# ProPrj_2026_05_12_drone_2026-05-23.net
KiCad netlist of a schematic drawn in EasyEDA Pro
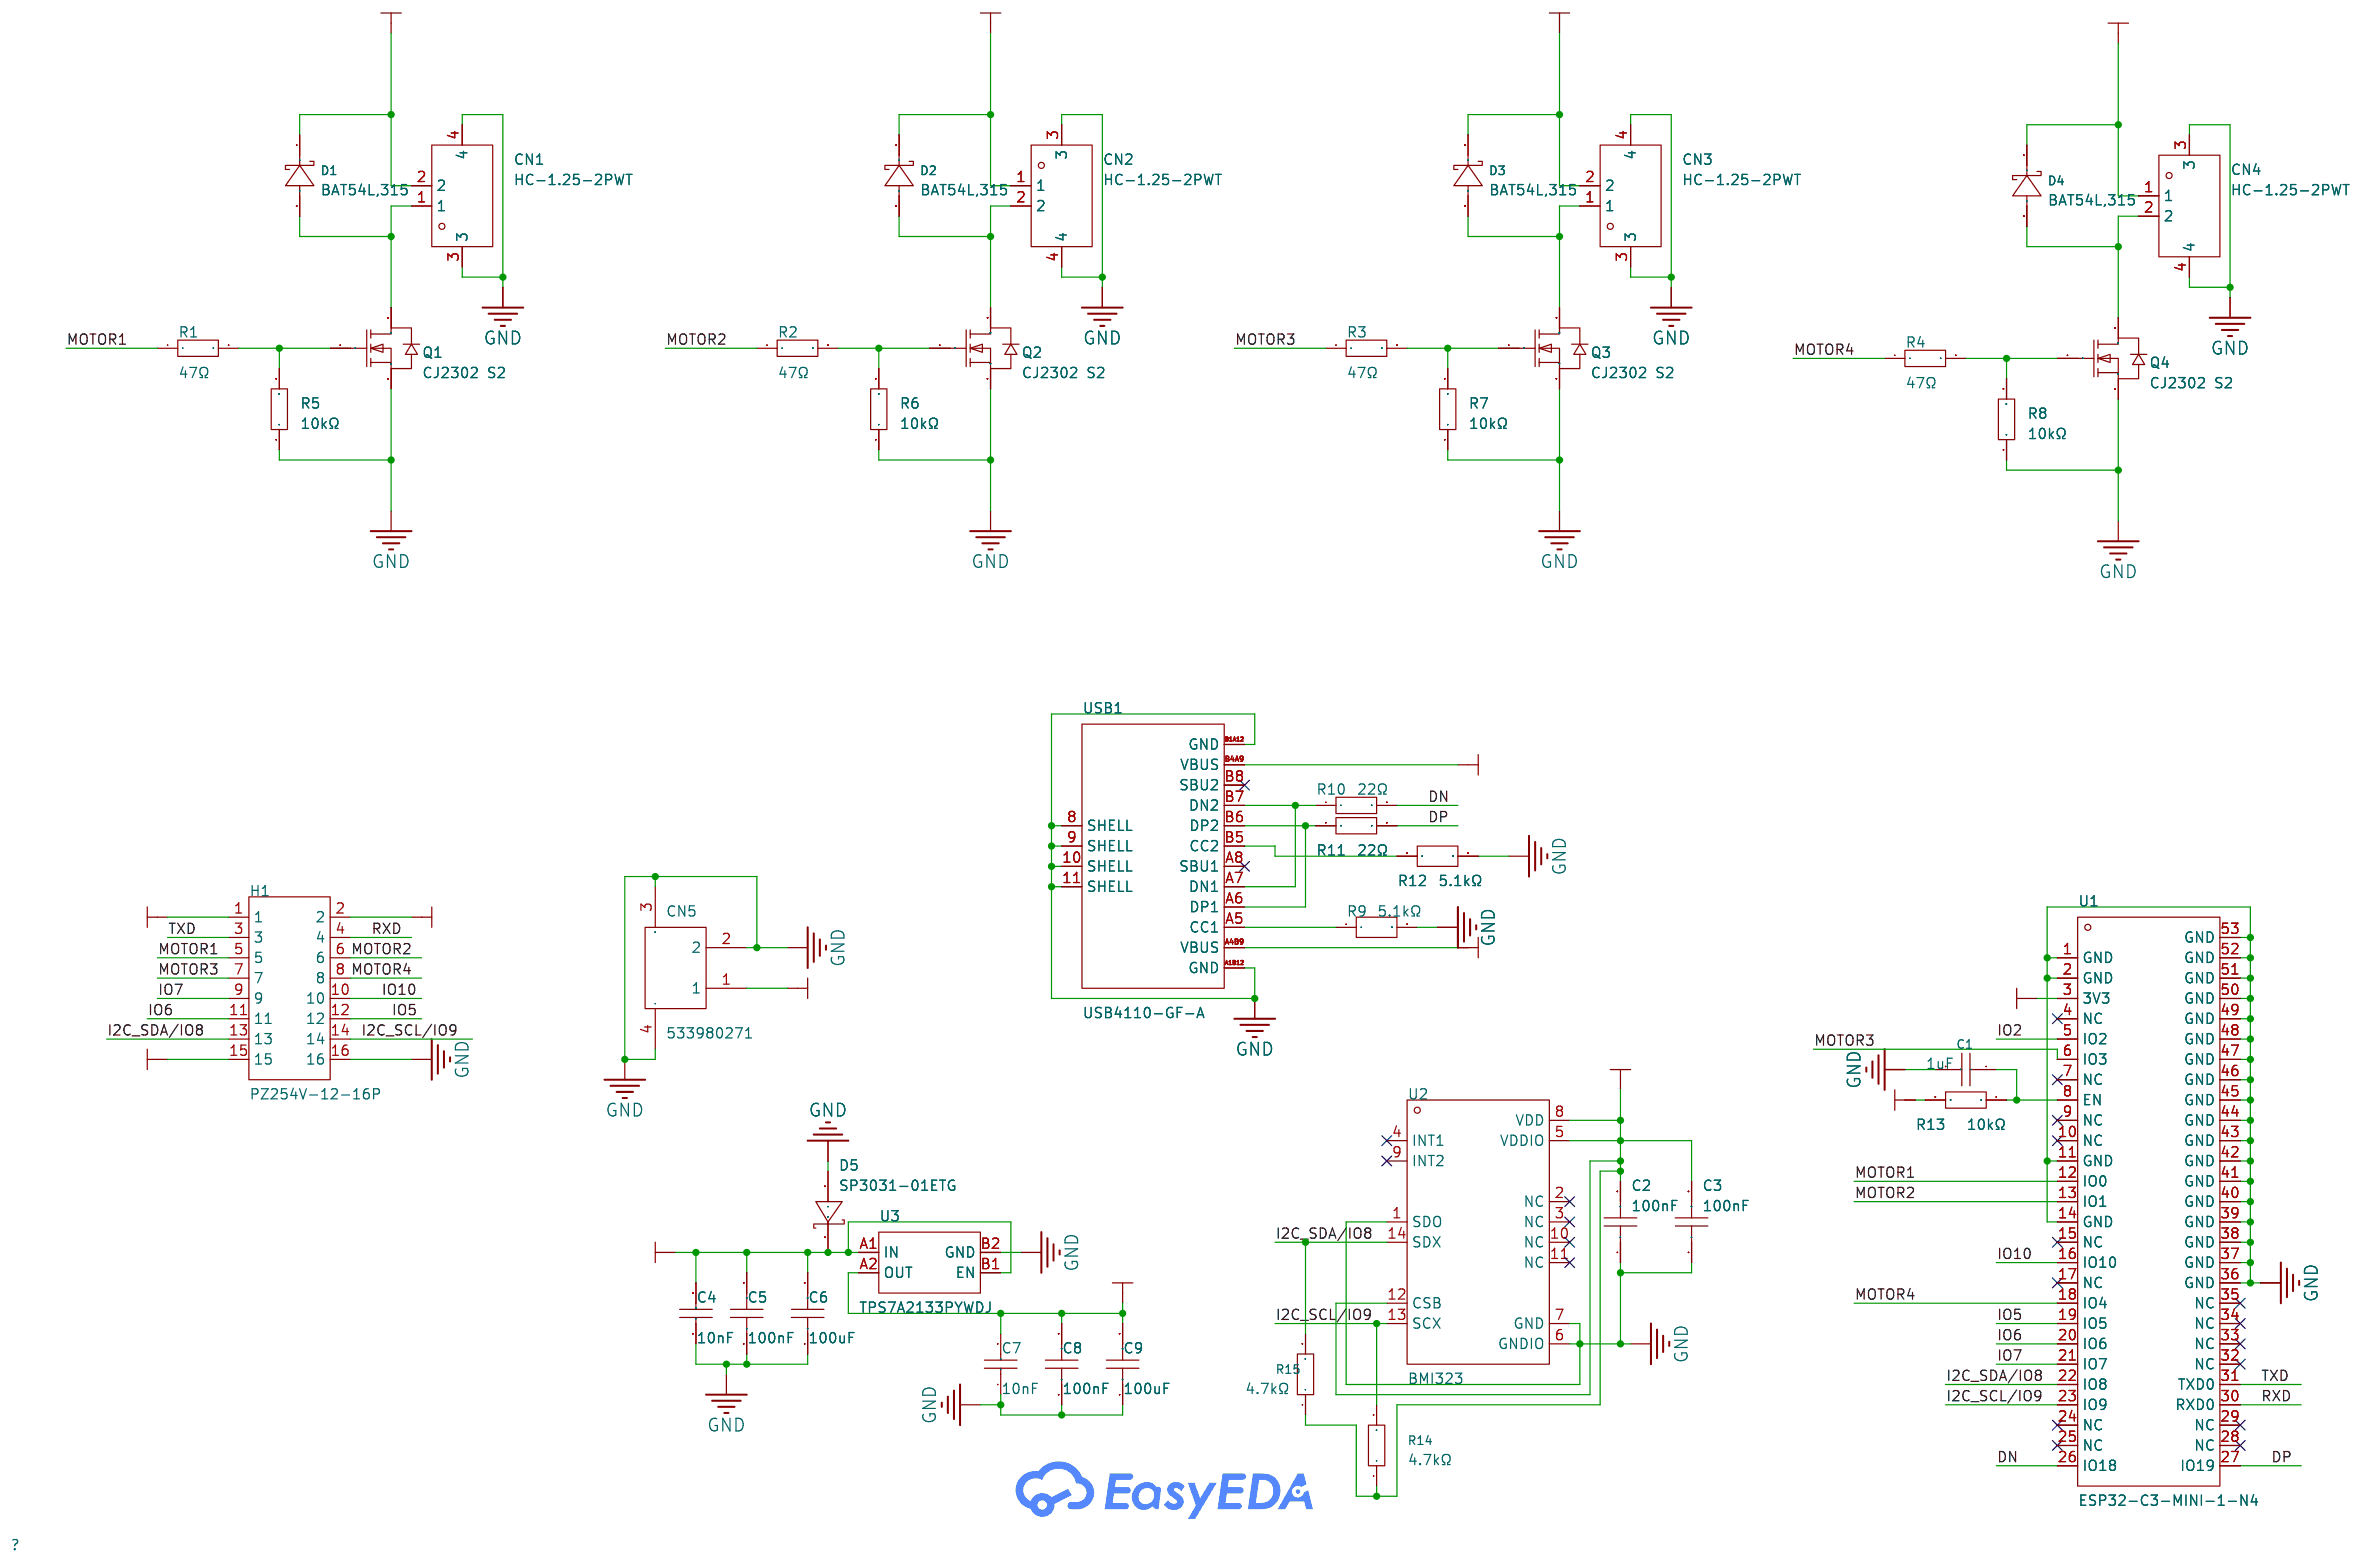
[diagram p0: schematic sheet]

(export (version "E")
  (design (tool "Eeschema 10.0.6"))
  (components
    (comp (ref "C1")
      (value "1uF")
      (footprint "easyedapro:C0402")
      (description "Capacitance:1uF Tolerance:±10% Tolerance:±10% Voltage Rating:16V Temperature Coefficient:X5R")
      (fields
        (field (name "Manufacturer Part") "CL05A105KO5NNNC")
        (field (name "Manufacturer") "SAMSUNG(三星)")
      )
      (libsource (lib "easyedapro") (part "CL05A105KO5NNNC"))
    )
    (comp (ref "C2")
      (value "100nF")
      (footprint "easyedapro:C0402")
      (fields
        (field (name "Manufacturer Part") "CL05B104KO5NNNC")
        (field (name "Manufacturer") "SAMSUNG(三星)")
      )
      (libsource (lib "easyedapro") (part "CL05B104KO5NNNC"))
    )
    (comp (ref "C3")
      (value "100nF")
      (footprint "easyedapro:C0402")
      (fields
        (field (name "Manufacturer Part") "CL05B104KO5NNNC")
        (field (name "Manufacturer") "SAMSUNG(三星)")
      )
      (libsource (lib "easyedapro") (part "CL05B104KO5NNNC"))
    )
    (comp (ref "C4")
      (value "10nF")
      (footprint "easyedapro:C0402")
      (description "Capacitance:10nF Tolerance:±10% Tolerance:±10% Voltage Rating:50V Temperature Coefficient:X7R")
      (fields
        (field (name "Manufacturer Part") "CL05B103KB5NNNC")
        (field (name "Manufacturer") "SAMSUNG(三星)")
      )
      (libsource (lib "easyedapro") (part "CL05B103KB5NNNC"))
    )
    (comp (ref "C5")
      (value "100nF")
      (footprint "easyedapro:C0603")
      (description "Capacitance:100nF Tolerance:±10% Tolerance:±10% Voltage Rating:50V Temperature Coefficient:X7R")
      (fields
        (field (name "Manufacturer Part") "CC0603KRX7R9BB104")
        (field (name "Manufacturer") "YAGEO(国巨)")
      )
      (libsource (lib "easyedapro") (part "CC0603KRX7R9BB104"))
    )
    (comp (ref "C6")
      (value "100uF")
      (footprint "easyedapro:C1206")
      (description "Capacitance:100uF Tolerance:±20% Tolerance:±20% Voltage Rating:10V Temperature Coefficient:X5R")
      (fields
        (field (name "Manufacturer Part") "HGC1206R5107M100NSPJ")
        (field (name "Manufacturer") "Chinocera(华瓷)")
      )
      (libsource (lib "easyedapro") (part "HGC1206R5107M100NSPJ"))
    )
    (comp (ref "C7")
      (value "10nF")
      (footprint "easyedapro:C0402")
      (description "Capacitance:10nF Tolerance:±10% Tolerance:±10% Voltage Rating:50V Temperature Coefficient:X7R")
      (fields
        (field (name "Manufacturer Part") "CL05B103KB5NNNC")
        (field (name "Manufacturer") "SAMSUNG(三星)")
      )
      (libsource (lib "easyedapro") (part "CL05B103KB5NNNC"))
    )
    (comp (ref "C8")
      (value "100nF")
      (footprint "easyedapro:C0603")
      (description "Capacitance:100nF Tolerance:±10% Tolerance:±10% Voltage Rating:50V Temperature Coefficient:X7R")
      (fields
        (field (name "Manufacturer Part") "CC0603KRX7R9BB104")
        (field (name "Manufacturer") "YAGEO(国巨)")
      )
      (libsource (lib "easyedapro") (part "CC0603KRX7R9BB104"))
    )
    (comp (ref "C9")
      (value "100uF")
      (footprint "easyedapro:C1206")
      (description "Capacitance:100uF Tolerance:±20% Tolerance:±20% Voltage Rating:10V Temperature Coefficient:X5R")
      (fields
        (field (name "Manufacturer Part") "HGC1206R5107M100NSPJ")
        (field (name "Manufacturer") "Chinocera(华瓷)")
      )
      (libsource (lib "easyedapro") (part "HGC1206R5107M100NSPJ"))
    )
    (comp (ref "CN1")
      (value "HC-1.25-2PWT")
      (footprint "easyedapro:CONN-SMD_2P-P1.25-HC-1.25-2PWT")
      (fields (field (name "Manufacturer") "HCTL(华灿天禄)"))
      (libsource (lib "easyedapro") (part "HC-1.25-2PWT"))
    )
    (comp (ref "CN2")
      (value "HC-1.25-2PWT")
      (footprint "easyedapro:CONN-SMD_2P-P1.25-HC-1.25-2PWT")
      (fields (field (name "Manufacturer") "HCTL(华灿天禄)"))
      (libsource (lib "easyedapro") (part "HC-1.25-2PWT"))
    )
    (comp (ref "CN3")
      (value "HC-1.25-2PWT")
      (footprint "easyedapro:CONN-SMD_2P-P1.25-HC-1.25-2PWT")
      (fields (field (name "Manufacturer") "HCTL(华灿天禄)"))
      (libsource (lib "easyedapro") (part "HC-1.25-2PWT"))
    )
    (comp (ref "CN4")
      (value "HC-1.25-2PWT")
      (footprint "easyedapro:CONN-SMD_2P-P1.25-HC-1.25-2PWT")
      (fields (field (name "Manufacturer") "HCTL(华灿天禄)"))
      (libsource (lib "easyedapro") (part "HC-1.25-2PWT"))
    )
    (comp (ref "CN5")
      (value "533980271")
      (footprint "easyedapro:CONN-SMD_2P-P1.25_053398-0X71")
      (fields (field (name "Manufacturer") "MOLEX"))
      (libsource (lib "easyedapro") (part "0533980271"))
    )
    (comp (ref "D1")
      (value "BAT54L,315")
      (footprint "easyedapro:DFN1006-2L-RD")
      (fields (field (name "Manufacturer") "Nexperia(安世)"))
      (libsource (lib "easyedapro") (part "BAT54L,315"))
    )
    (comp (ref "D2")
      (value "BAT54L,315")
      (footprint "easyedapro:DFN1006-2L-RD")
      (fields (field (name "Manufacturer") "Nexperia(安世)"))
      (libsource (lib "easyedapro") (part "BAT54L,315"))
    )
    (comp (ref "D3")
      (value "BAT54L,315")
      (footprint "easyedapro:DFN1006-2L-RD")
      (fields (field (name "Manufacturer") "Nexperia(安世)"))
      (libsource (lib "easyedapro") (part "BAT54L,315"))
    )
    (comp (ref "D4")
      (value "BAT54L,315")
      (footprint "easyedapro:DFN1006-2L-RD")
      (fields (field (name "Manufacturer") "Nexperia(安世)"))
      (libsource (lib "easyedapro") (part "BAT54L,315"))
    )
    (comp (ref "D5")
      (value "SP3031-01ETG")
      (footprint "easyedapro:SOD-882_L1.0-W0.6-RD")
      (fields (field (name "Manufacturer") "Littelfuse(美国力特)"))
      (libsource (lib "easyedapro") (part "SP3031-01ETG"))
    )
    (comp (ref "H1")
      (value "PZ254V-12-16P")
      (footprint "easyedapro:HDR-TH_16P-P2.54-V-M-R2-C8-S2.54")
      (fields (field (name "Manufacturer") "XFCN(兴飞)"))
      (libsource (lib "easyedapro") (part "PZ254V-12-16P"))
    )
    (comp (ref "Q1")
      (value "CJ2302 S2")
      (footprint "easyedapro:SOT-23-3_L3.0-W1.7-P0.95-LS2.9-BR")
      (fields (field (name "Manufacturer") "CJ(江苏长电/长晶)"))
      (libsource (lib "easyedapro") (part "CJ2302 S2"))
    )
    (comp (ref "Q2")
      (value "CJ2302 S2")
      (footprint "easyedapro:SOT-23-3_L3.0-W1.7-P0.95-LS2.9-BR")
      (fields (field (name "Manufacturer") "CJ(江苏长电/长晶)"))
      (libsource (lib "easyedapro") (part "CJ2302 S2"))
    )
    (comp (ref "Q3")
      (value "CJ2302 S2")
      (footprint "easyedapro:SOT-23-3_L3.0-W1.7-P0.95-LS2.9-BR")
      (fields (field (name "Manufacturer") "CJ(江苏长电/长晶)"))
      (libsource (lib "easyedapro") (part "CJ2302 S2"))
    )
    (comp (ref "Q4")
      (value "CJ2302 S2")
      (footprint "easyedapro:SOT-23-3_L3.0-W1.7-P0.95-LS2.9-BR")
      (fields (field (name "Manufacturer") "CJ(江苏长电/长晶)"))
      (libsource (lib "easyedapro") (part "CJ2302 S2"))
    )
    (comp (ref "R1")
      (value "47Ω")
      (footprint "easyedapro:R0402")
      (fields (field (name "Manufacturer Part") "RC0402FR-0747RL") (field (name "Manufacturer") "YAGEO(国巨)"))
      (libsource (lib "easyedapro") (part "RC0402FR-0747RL"))
    )
    (comp (ref "R2")
      (value "47Ω")
      (footprint "easyedapro:R0402")
      (fields (field (name "Manufacturer Part") "RC0402FR-0747RL") (field (name "Manufacturer") "YAGEO(国巨)"))
      (libsource (lib "easyedapro") (part "RC0402FR-0747RL"))
    )
    (comp (ref "R3")
      (value "47Ω")
      (footprint "easyedapro:R0402")
      (fields (field (name "Manufacturer Part") "RC0402FR-0747RL") (field (name "Manufacturer") "YAGEO(国巨)"))
      (libsource (lib "easyedapro") (part "RC0402FR-0747RL"))
    )
    (comp (ref "R4")
      (value "47Ω")
      (footprint "easyedapro:R0402")
      (fields (field (name "Manufacturer Part") "RC0402FR-0747RL") (field (name "Manufacturer") "YAGEO(国巨)"))
      (libsource (lib "easyedapro") (part "RC0402FR-0747RL"))
    )
    (comp (ref "R5")
      (value "10kΩ")
      (footprint "easyedapro:R0402")
      (fields (field (name "Manufacturer Part") "RC0402FR-0710KL") (field (name "Manufacturer") "YAGEO(国巨)"))
      (libsource (lib "easyedapro") (part "RC0402FR-0710KL"))
    )
    (comp (ref "R6")
      (value "10kΩ")
      (footprint "easyedapro:R0402")
      (fields (field (name "Manufacturer Part") "RC0402FR-0710KL") (field (name "Manufacturer") "YAGEO(国巨)"))
      (libsource (lib "easyedapro") (part "RC0402FR-0710KL"))
    )
    (comp (ref "R7")
      (value "10kΩ")
      (footprint "easyedapro:R0402")
      (fields (field (name "Manufacturer Part") "RC0402FR-0710KL") (field (name "Manufacturer") "YAGEO(国巨)"))
      (libsource (lib "easyedapro") (part "RC0402FR-0710KL"))
    )
    (comp (ref "R8")
      (value "10kΩ")
      (footprint "easyedapro:R0402")
      (fields (field (name "Manufacturer Part") "RC0402FR-0710KL") (field (name "Manufacturer") "YAGEO(国巨)"))
      (libsource (lib "easyedapro") (part "RC0402FR-0710KL"))
    )
    (comp (ref "R9")
      (value "5.1kΩ")
      (footprint "easyedapro:R0603")
      (fields (field (name "Manufacturer Part") "FRC0603F5101TS") (field (name "Manufacturer") "FOJAN(富捷)"))
      (libsource (lib "easyedapro") (part "FRC0603F5101TS"))
    )
    (comp (ref "R10")
      (value "22Ω")
      (footprint "easyedapro:R0603")
      (fields
        (field (name "Manufacturer Part") "0603WAF220JT5E")
        (field (name "Manufacturer") "UNI-ROYAL(厚声)")
      )
      (libsource (lib "easyedapro") (part "0603WAF220JT5E"))
    )
    (comp (ref "R11")
      (value "22Ω")
      (footprint "easyedapro:R0603")
      (fields
        (field (name "Manufacturer Part") "0603WAF220JT5E")
        (field (name "Manufacturer") "UNI-ROYAL(厚声)")
      )
      (libsource (lib "easyedapro") (part "0603WAF220JT5E"))
    )
    (comp (ref "R12")
      (value "5.1kΩ")
      (footprint "easyedapro:R0603")
      (fields (field (name "Manufacturer Part") "FRC0603F5101TS") (field (name "Manufacturer") "FOJAN(富捷)"))
      (libsource (lib "easyedapro") (part "FRC0603F5101TS"))
    )
    (comp (ref "R13")
      (value "10kΩ")
      (footprint "easyedapro:R0603")
      (fields (field (name "Manufacturer Part") "RC0603FR-0710KL") (field (name "Manufacturer") "YAGEO(国巨)"))
      (libsource (lib "easyedapro") (part "RC0603FR-0710KL"))
    )
    (comp (ref "R14")
      (value "4.7kΩ")
      (footprint "easyedapro:R0402")
      (fields
        (field (name "Manufacturer Part") "0402WGF4701TCE")
        (field (name "Manufacturer") "UNI-ROYAL(厚声)")
      )
      (libsource (lib "easyedapro") (part "0402WGF4701TCE"))
    )
    (comp (ref "R15")
      (value "4.7kΩ")
      (footprint "easyedapro:R0402")
      (fields
        (field (name "Manufacturer Part") "0402WGF4701TCE")
        (field (name "Manufacturer") "UNI-ROYAL(厚声)")
      )
      (libsource (lib "easyedapro") (part "0402WGF4701TCE"))
    )
    (comp (ref "U1")
      (value "ESP32-C3-MINI-1-N4")
      (footprint "easyedapro:WIFIM-SMD_ESP32-C3-MINI-1")
      (fields (field (name "Manufacturer") "ESPRESSIF(乐鑫)"))
      (libsource (lib "easyedapro") (part "ESP32-C3-MINI-1-N4"))
    )
    (comp (ref "U2")
      (value "BMI323")
      (footprint "easyedapro:LGA-14_L3.0-W2.5-P0.50-TL_QMI8658A")
      (fields (field (name "Manufacturer") "Bosch(博世)"))
      (libsource (lib "easyedapro") (part "BMI323"))
    )
    (comp (ref "U3")
      (value "TPS7A2133PYWDJ")
      (footprint "easyedapro:DSBGA-4_L0.6-W0.6-P0.35-TL")
      (fields (field (name "Manufacturer") "TI(德州仪器)"))
      (libsource (lib "easyedapro") (part "TPS7A2133PYWDJ"))
    )
    (comp (ref "USB1")
      (value "USB4110-GF-A")
      (footprint "easyedapro:USB-C-SMD_TYPE-C-16P-USB4110-GF-A")
      (fields (field (name "Manufacturer") "GCT"))
      (libsource (lib "easyedapro") (part "USB4110-GF-A"))
    )
  )
  (nets
    (net (code "1") (name "/DN") (class "Default")
      (node (ref "R10") (pin "2") (pinfunction "2_2") (pintype "input"))
      (node (ref "U1") (pin "26") (pinfunction "IO18_26") (pintype "unspecified"))
    )
    (net (code "2") (name "/DP") (class "Default")
      (node (ref "R11") (pin "2") (pinfunction "2_2") (pintype "input"))
      (node (ref "U1") (pin "27") (pinfunction "IO19_27") (pintype "unspecified"))
    )
    (net (code "3") (name "/I2C_SCL{slash}IO9") (class "Default")
      (node (ref "H1") (pin "14") (pinfunction "14_14") (pintype "unspecified"))
      (node (ref "R14") (pin "2") (pinfunction "2_2") (pintype "input"))
      (node (ref "U1") (pin "23") (pinfunction "IO9_23") (pintype "unspecified"))
      (node (ref "U2") (pin "13") (pinfunction "SCX_13") (pintype "unspecified"))
    )
    (net (code "4") (name "/I2C_SDA{slash}IO8") (class "Default")
      (node (ref "H1") (pin "13") (pinfunction "13_13") (pintype "unspecified"))
      (node (ref "R15") (pin "2") (pinfunction "2_2") (pintype "input"))
      (node (ref "U1") (pin "22") (pinfunction "IO8_22") (pintype "unspecified"))
      (node (ref "U2") (pin "14") (pinfunction "SDX_14") (pintype "unspecified"))
    )
    (net (code "5") (name "/IO2") (class "Default")
      (node (ref "U1") (pin "5") (pinfunction "IO2_5") (pintype "unspecified"))
    )
    (net (code "6") (name "/IO5") (class "Default")
      (node (ref "H1") (pin "12") (pinfunction "12_12") (pintype "unspecified"))
      (node (ref "U1") (pin "19") (pinfunction "IO5_19") (pintype "unspecified"))
    )
    (net (code "7") (name "/IO6") (class "Default")
      (node (ref "H1") (pin "11") (pinfunction "11_11") (pintype "unspecified"))
      (node (ref "U1") (pin "20") (pinfunction "IO6_20") (pintype "unspecified"))
    )
    (net (code "8") (name "/IO7") (class "Default")
      (node (ref "H1") (pin "9") (pinfunction "9_9") (pintype "unspecified"))
      (node (ref "U1") (pin "21") (pinfunction "IO7_21") (pintype "unspecified"))
    )
    (net (code "9") (name "/IO10") (class "Default")
      (node (ref "H1") (pin "10") (pinfunction "10_10") (pintype "unspecified"))
      (node (ref "U1") (pin "16") (pinfunction "IO10_16") (pintype "unspecified"))
    )
    (net (code "10") (name "/MOTOR1") (class "Default")
      (node (ref "H1") (pin "5") (pinfunction "5_5") (pintype "unspecified"))
      (node (ref "R1") (pin "1") (pinfunction "1_1") (pintype "input"))
      (node (ref "U1") (pin "12") (pinfunction "IO0_12") (pintype "unspecified"))
    )
    (net (code "11") (name "/MOTOR2") (class "Default")
      (node (ref "H1") (pin "6") (pinfunction "6_6") (pintype "unspecified"))
      (node (ref "R2") (pin "1") (pinfunction "1_1") (pintype "input"))
      (node (ref "U1") (pin "13") (pinfunction "IO1_13") (pintype "unspecified"))
    )
    (net (code "12") (name "/MOTOR3") (class "Default")
      (node (ref "H1") (pin "7") (pinfunction "7_7") (pintype "unspecified"))
      (node (ref "R3") (pin "1") (pinfunction "1_1") (pintype "input"))
      (node (ref "U1") (pin "6") (pinfunction "IO3_6") (pintype "unspecified"))
    )
    (net (code "13") (name "/MOTOR4") (class "Default")
      (node (ref "H1") (pin "8") (pinfunction "8_8") (pintype "unspecified"))
      (node (ref "R4") (pin "1") (pinfunction "1_1") (pintype "input"))
      (node (ref "U1") (pin "18") (pinfunction "IO4_18") (pintype "unspecified"))
    )
    (net (code "14") (name "/RXD") (class "Default")
      (node (ref "H1") (pin "4") (pinfunction "4_4") (pintype "unspecified"))
      (node (ref "U1") (pin "30") (pinfunction "RXD0_30") (pintype "unspecified"))
    )
    (net (code "15") (name "/TXD") (class "Default")
      (node (ref "H1") (pin "3") (pinfunction "3_3") (pintype "unspecified"))
      (node (ref "U1") (pin "31") (pinfunction "TXD0_31") (pintype "unspecified"))
    )
    (net (code "16") (name "3V3") (class "Default")
      (node (ref "C2") (pin "2") (pinfunction "2_2") (pintype "unspecified"))
      (node (ref "C3") (pin "2") (pinfunction "2_2") (pintype "unspecified"))
      (node (ref "C7") (pin "2") (pinfunction "2_2") (pintype "input"))
      (node (ref "C8") (pin "2") (pinfunction "2_2") (pintype "unspecified"))
      (node (ref "C9") (pin "2") (pinfunction "2_2") (pintype "unspecified"))
      (node (ref "H1") (pin "15") (pinfunction "15_15") (pintype "unspecified"))
      (node (ref "R13") (pin "2") (pinfunction "2_2") (pintype "input"))
      (node (ref "R14") (pin "1") (pinfunction "1_1") (pintype "input"))
      (node (ref "R15") (pin "1") (pinfunction "1_1") (pintype "input"))
      (node (ref "U1") (pin "3") (pinfunction "3V3_3") (pintype "unspecified"))
      (node (ref "U2") (pin "12") (pinfunction "CSB_12") (pintype "unspecified"))
      (node (ref "U2") (pin "5") (pinfunction "VDDIO_5") (pintype "unspecified"))
      (node (ref "U2") (pin "8") (pinfunction "VDD_8") (pintype "unspecified"))
      (node (ref "U3") (pin "A2") (pinfunction "OUT_A2") (pintype "unspecified"))
    )
    (net (code "17") (name "GND") (class "Default")
      (node (ref "C1") (pin "2") (pinfunction "2_2") (pintype "input"))
      (node (ref "C2") (pin "1") (pinfunction "1_1") (pintype "unspecified"))
      (node (ref "C3") (pin "1") (pinfunction "1_1") (pintype "unspecified"))
      (node (ref "C4") (pin "1") (pinfunction "1_1") (pintype "input"))
      (node (ref "C5") (pin "1") (pinfunction "1_1") (pintype "unspecified"))
      (node (ref "C6") (pin "1") (pinfunction "1_1") (pintype "unspecified"))
      (node (ref "C7") (pin "1") (pinfunction "1_1") (pintype "input"))
      (node (ref "C8") (pin "1") (pinfunction "1_1") (pintype "unspecified"))
      (node (ref "C9") (pin "1") (pinfunction "1_1") (pintype "unspecified"))
      (node (ref "CN1") (pin "3") (pinfunction "3_3") (pintype "unspecified"))
      (node (ref "CN1") (pin "4") (pinfunction "4_4") (pintype "unspecified"))
      (node (ref "CN2") (pin "3") (pinfunction "3_3") (pintype "unspecified"))
      (node (ref "CN2") (pin "4") (pinfunction "4_4") (pintype "unspecified"))
      (node (ref "CN3") (pin "3") (pinfunction "3_3") (pintype "unspecified"))
      (node (ref "CN3") (pin "4") (pinfunction "4_4") (pintype "unspecified"))
      (node (ref "CN4") (pin "3") (pinfunction "3_3") (pintype "unspecified"))
      (node (ref "CN4") (pin "4") (pinfunction "4_4") (pintype "unspecified"))
      (node (ref "CN5") (pin "2") (pinfunction "2_2") (pintype "unspecified"))
      (node (ref "CN5") (pin "3") (pinfunction "3_3") (pintype "unspecified"))
      (node (ref "CN5") (pin "4") (pinfunction "4_4") (pintype "unspecified"))
      (node (ref "D5") (pin "2") (pinfunction "A_2") (pintype "unspecified"))
      (node (ref "H1") (pin "16") (pinfunction "16_16") (pintype "unspecified"))
      (node (ref "Q1") (pin "2") (pinfunction "S_2") (pintype "unspecified"))
      (node (ref "Q2") (pin "2") (pinfunction "S_2") (pintype "unspecified"))
      (node (ref "Q3") (pin "2") (pinfunction "S_2") (pintype "unspecified"))
      (node (ref "Q4") (pin "2") (pinfunction "S_2") (pintype "unspecified"))
      (node (ref "R12") (pin "2") (pinfunction "2_2") (pintype "unspecified"))
      (node (ref "R5") (pin "1") (pinfunction "1_1") (pintype "input"))
      (node (ref "R6") (pin "1") (pinfunction "1_1") (pintype "input"))
      (node (ref "R7") (pin "1") (pinfunction "1_1") (pintype "input"))
      (node (ref "R8") (pin "1") (pinfunction "1_1") (pintype "input"))
      (node (ref "R9") (pin "2") (pinfunction "2_2") (pintype "unspecified"))
      (node (ref "U1") (pin "1") (pinfunction "GND_1") (pintype "unspecified"))
      (node (ref "U1") (pin "11") (pinfunction "GND_11") (pintype "unspecified"))
      (node (ref "U1") (pin "14") (pinfunction "GND_14") (pintype "unspecified"))
      (node (ref "U1") (pin "2") (pinfunction "GND_2") (pintype "unspecified"))
      (node (ref "U1") (pin "36") (pinfunction "GND_36") (pintype "unspecified"))
      (node (ref "U1") (pin "37") (pinfunction "GND_37") (pintype "unspecified"))
      (node (ref "U1") (pin "38") (pinfunction "GND_38") (pintype "unspecified"))
      (node (ref "U1") (pin "39") (pinfunction "GND_39") (pintype "unspecified"))
      (node (ref "U1") (pin "40") (pinfunction "GND_40") (pintype "unspecified"))
      (node (ref "U1") (pin "41") (pinfunction "GND_41") (pintype "unspecified"))
      (node (ref "U1") (pin "42") (pinfunction "GND_42") (pintype "unspecified"))
      (node (ref "U1") (pin "43") (pinfunction "GND_43") (pintype "unspecified"))
      (node (ref "U1") (pin "44") (pinfunction "GND_44") (pintype "unspecified"))
      (node (ref "U1") (pin "45") (pinfunction "GND_45") (pintype "unspecified"))
      (node (ref "U1") (pin "46") (pinfunction "GND_46") (pintype "unspecified"))
      (node (ref "U1") (pin "47") (pinfunction "GND_47") (pintype "unspecified"))
      (node (ref "U1") (pin "48") (pinfunction "GND_48") (pintype "unspecified"))
      (node (ref "U1") (pin "49") (pinfunction "GND_49") (pintype "unspecified"))
      (node (ref "U1") (pin "50") (pinfunction "GND_50") (pintype "unspecified"))
      (node (ref "U1") (pin "51") (pinfunction "GND_51") (pintype "unspecified"))
      (node (ref "U1") (pin "52") (pinfunction "GND_52") (pintype "unspecified"))
      (node (ref "U1") (pin "53") (pinfunction "GND_53") (pintype "unspecified"))
      (node (ref "U2") (pin "1") (pinfunction "SDO_1") (pintype "unspecified"))
      (node (ref "U2") (pin "6") (pinfunction "GNDIO_6") (pintype "unspecified"))
      (node (ref "U2") (pin "7") (pinfunction "GND_7") (pintype "unspecified"))
      (node (ref "U3") (pin "B2") (pinfunction "GND_B2") (pintype "unspecified"))
      (node (ref "USB1") (pin "10") (pinfunction "SHELL_10") (pintype "unspecified"))
      (node (ref "USB1") (pin "11") (pinfunction "SHELL_11") (pintype "unspecified"))
      (node (ref "USB1") (pin "8") (pinfunction "SHELL_8") (pintype "unspecified"))
      (node (ref "USB1") (pin "9") (pinfunction "SHELL_9") (pintype "unspecified"))
      (node (ref "USB1") (pin "A1B12") (pinfunction "GND_A1B12") (pintype "unspecified"))
      (node (ref "USB1") (pin "B1A12") (pinfunction "GND_B1A12") (pintype "unspecified"))
    )
    (net (code "18") (name "Net-(D1-A)") (class "Default")
      (node (ref "CN1") (pin "1") (pinfunction "1_1") (pintype "unspecified"))
      (node (ref "D1") (pin "2") (pinfunction "A_2") (pintype "input"))
      (node (ref "Q1") (pin "3") (pinfunction "D_3") (pintype "unspecified"))
    )
    (net (code "19") (name "Net-(D2-A)") (class "Default")
      (node (ref "CN2") (pin "2") (pinfunction "2_2") (pintype "unspecified"))
      (node (ref "D2") (pin "2") (pinfunction "A_2") (pintype "input"))
      (node (ref "Q2") (pin "3") (pinfunction "D_3") (pintype "unspecified"))
    )
    (net (code "20") (name "Net-(D3-A)") (class "Default")
      (node (ref "CN3") (pin "1") (pinfunction "1_1") (pintype "unspecified"))
      (node (ref "D3") (pin "2") (pinfunction "A_2") (pintype "input"))
      (node (ref "Q3") (pin "3") (pinfunction "D_3") (pintype "unspecified"))
    )
    (net (code "21") (name "Net-(D4-A)") (class "Default")
      (node (ref "CN4") (pin "2") (pinfunction "2_2") (pintype "unspecified"))
      (node (ref "D4") (pin "2") (pinfunction "A_2") (pintype "input"))
      (node (ref "Q4") (pin "3") (pinfunction "D_3") (pintype "unspecified"))
    )
    (net (code "22") (name "Net-(Q1-G)") (class "Default")
      (node (ref "Q1") (pin "1") (pinfunction "G_1") (pintype "unspecified"))
      (node (ref "R1") (pin "2") (pinfunction "2_2") (pintype "input"))
      (node (ref "R5") (pin "2") (pinfunction "2_2") (pintype "input"))
    )
    (net (code "23") (name "Net-(Q2-G)") (class "Default")
      (node (ref "Q2") (pin "1") (pinfunction "G_1") (pintype "unspecified"))
      (node (ref "R2") (pin "2") (pinfunction "2_2") (pintype "input"))
      (node (ref "R6") (pin "2") (pinfunction "2_2") (pintype "input"))
    )
    (net (code "24") (name "Net-(Q3-G)") (class "Default")
      (node (ref "Q3") (pin "1") (pinfunction "G_1") (pintype "unspecified"))
      (node (ref "R3") (pin "2") (pinfunction "2_2") (pintype "input"))
      (node (ref "R7") (pin "2") (pinfunction "2_2") (pintype "input"))
    )
    (net (code "25") (name "Net-(Q4-G)") (class "Default")
      (node (ref "Q4") (pin "1") (pinfunction "G_1") (pintype "unspecified"))
      (node (ref "R4") (pin "2") (pinfunction "2_2") (pintype "input"))
      (node (ref "R8") (pin "2") (pinfunction "2_2") (pintype "input"))
    )
    (net (code "26") (name "Net-(U1-EN)") (class "Default")
      (node (ref "C1") (pin "1") (pinfunction "1_1") (pintype "input"))
      (node (ref "R13") (pin "1") (pinfunction "1_1") (pintype "input"))
      (node (ref "U1") (pin "8") (pinfunction "EN_8") (pintype "unspecified"))
    )
    (net (code "27") (name "Net-(USB1-CC1)") (class "Default")
      (node (ref "R9") (pin "1") (pinfunction "1_1") (pintype "unspecified"))
      (node (ref "USB1") (pin "A5") (pinfunction "CC1_A5") (pintype "unspecified"))
    )
    (net (code "28") (name "Net-(USB1-CC2)") (class "Default")
      (node (ref "R12") (pin "1") (pinfunction "1_1") (pintype "unspecified"))
      (node (ref "USB1") (pin "B5") (pinfunction "CC2_B5") (pintype "unspecified"))
    )
    (net (code "29") (name "Net-(USB1-DN1)") (class "Default")
      (node (ref "R10") (pin "1") (pinfunction "1_1") (pintype "input"))
      (node (ref "USB1") (pin "A7") (pinfunction "DN1_A7") (pintype "unspecified"))
      (node (ref "USB1") (pin "B7") (pinfunction "DN2_B7") (pintype "unspecified"))
    )
    (net (code "30") (name "Net-(USB1-DP1)") (class "Default")
      (node (ref "R11") (pin "1") (pinfunction "1_1") (pintype "input"))
      (node (ref "USB1") (pin "A6") (pinfunction "DP1_A6") (pintype "unspecified"))
      (node (ref "USB1") (pin "B6") (pinfunction "DP2_B6") (pintype "unspecified"))
    )
    (net (code "31") (name "VBAT") (class "Default")
      (node (ref "CN1") (pin "2") (pinfunction "2_2") (pintype "unspecified"))
      (node (ref "CN2") (pin "1") (pinfunction "1_1") (pintype "unspecified"))
      (node (ref "CN3") (pin "2") (pinfunction "2_2") (pintype "unspecified"))
      (node (ref "CN4") (pin "1") (pinfunction "1_1") (pintype "unspecified"))
      (node (ref "CN5") (pin "1") (pinfunction "1_1") (pintype "unspecified"))
      (node (ref "D1") (pin "1") (pinfunction "K_1") (pintype "input"))
      (node (ref "D2") (pin "1") (pinfunction "K_1") (pintype "input"))
      (node (ref "D3") (pin "1") (pinfunction "K_1") (pintype "input"))
      (node (ref "D4") (pin "1") (pinfunction "K_1") (pintype "input"))
      (node (ref "H1") (pin "1") (pinfunction "1_1") (pintype "unspecified"))
    )
    (net (code "32") (name "VCC") (class "Default")
      (node (ref "C4") (pin "2") (pinfunction "2_2") (pintype "input"))
      (node (ref "C5") (pin "2") (pinfunction "2_2") (pintype "unspecified"))
      (node (ref "C6") (pin "2") (pinfunction "2_2") (pintype "unspecified"))
      (node (ref "D5") (pin "1") (pinfunction "K_1") (pintype "unspecified"))
      (node (ref "H1") (pin "2") (pinfunction "2_2") (pintype "unspecified"))
      (node (ref "U3") (pin "A1") (pinfunction "IN_A1") (pintype "unspecified"))
      (node (ref "U3") (pin "B1") (pinfunction "EN_B1") (pintype "unspecified"))
      (node (ref "USB1") (pin "A4B9") (pinfunction "VBUS_A4B9") (pintype "unspecified"))
      (node (ref "USB1") (pin "B4A9") (pinfunction "VBUS_B4A9") (pintype "unspecified"))
    )
    (net (code "33") (name "unconnected-(U1-NC-Pad4)") (class "Default")
      (node (ref "U1") (pin "4") (pinfunction "NC_4") (pintype "unspecified+no_connect"))
    )
    (net (code "34") (name "unconnected-(U1-NC-Pad7)") (class "Default")
      (node (ref "U1") (pin "7") (pinfunction "NC_7") (pintype "unspecified+no_connect"))
    )
    (net (code "35") (name "unconnected-(U1-NC-Pad9)") (class "Default")
      (node (ref "U1") (pin "9") (pinfunction "NC_9") (pintype "unspecified+no_connect"))
    )
    (net (code "36") (name "unconnected-(U1-NC-Pad10)") (class "Default")
      (node (ref "U1") (pin "10") (pinfunction "NC_10") (pintype "unspecified+no_connect"))
    )
    (net (code "37") (name "unconnected-(U1-NC-Pad15)") (class "Default")
      (node (ref "U1") (pin "15") (pinfunction "NC_15") (pintype "unspecified+no_connect"))
    )
    (net (code "38") (name "unconnected-(U1-NC-Pad17)") (class "Default")
      (node (ref "U1") (pin "17") (pinfunction "NC_17") (pintype "unspecified+no_connect"))
    )
    (net (code "39") (name "unconnected-(U1-NC-Pad24)") (class "Default")
      (node (ref "U1") (pin "24") (pinfunction "NC_24") (pintype "unspecified+no_connect"))
    )
    (net (code "40") (name "unconnected-(U1-NC-Pad25)") (class "Default")
      (node (ref "U1") (pin "25") (pinfunction "NC_25") (pintype "unspecified+no_connect"))
    )
    (net (code "41") (name "unconnected-(U1-NC-Pad28)") (class "Default")
      (node (ref "U1") (pin "28") (pinfunction "NC_28") (pintype "unspecified+no_connect"))
    )
    (net (code "42") (name "unconnected-(U1-NC-Pad29)") (class "Default")
      (node (ref "U1") (pin "29") (pinfunction "NC_29") (pintype "unspecified+no_connect"))
    )
    (net (code "43") (name "unconnected-(U1-NC-Pad32)") (class "Default")
      (node (ref "U1") (pin "32") (pinfunction "NC_32") (pintype "unspecified+no_connect"))
    )
    (net (code "44") (name "unconnected-(U1-NC-Pad33)") (class "Default")
      (node (ref "U1") (pin "33") (pinfunction "NC_33") (pintype "unspecified+no_connect"))
    )
    (net (code "45") (name "unconnected-(U1-NC-Pad34)") (class "Default")
      (node (ref "U1") (pin "34") (pinfunction "NC_34") (pintype "unspecified+no_connect"))
    )
    (net (code "46") (name "unconnected-(U1-NC-Pad35)") (class "Default")
      (node (ref "U1") (pin "35") (pinfunction "NC_35") (pintype "unspecified+no_connect"))
    )
    (net (code "47") (name "unconnected-(U2-INT1-Pad4)") (class "Default")
      (node (ref "U2") (pin "4") (pinfunction "INT1_4") (pintype "unspecified+no_connect"))
    )
    (net (code "48") (name "unconnected-(U2-INT2-Pad9)") (class "Default")
      (node (ref "U2") (pin "9") (pinfunction "INT2_9") (pintype "unspecified+no_connect"))
    )
    (net (code "49") (name "unconnected-(U2-NC-Pad2)") (class "Default")
      (node (ref "U2") (pin "2") (pinfunction "NC_2") (pintype "unspecified+no_connect"))
    )
    (net (code "50") (name "unconnected-(U2-NC-Pad3)") (class "Default")
      (node (ref "U2") (pin "3") (pinfunction "NC_3") (pintype "unspecified+no_connect"))
    )
    (net (code "51") (name "unconnected-(U2-NC-Pad10)") (class "Default")
      (node (ref "U2") (pin "10") (pinfunction "NC_10") (pintype "unspecified+no_connect"))
    )
    (net (code "52") (name "unconnected-(U2-NC-Pad11)") (class "Default")
      (node (ref "U2") (pin "11") (pinfunction "NC_11") (pintype "unspecified+no_connect"))
    )
    (net (code "53") (name "unconnected-(USB1-SBU1-PadA8)") (class "Default")
      (node (ref "USB1") (pin "A8") (pinfunction "SBU1_A8") (pintype "unspecified+no_connect"))
    )
    (net (code "54") (name "unconnected-(USB1-SBU2-PadB8)") (class "Default")
      (node (ref "USB1") (pin "B8") (pinfunction "SBU2_B8") (pintype "unspecified+no_connect"))
    )
  )
)
